# Arduino_Shield.net
KiCad netlist of a schematic drawn in EAGLE
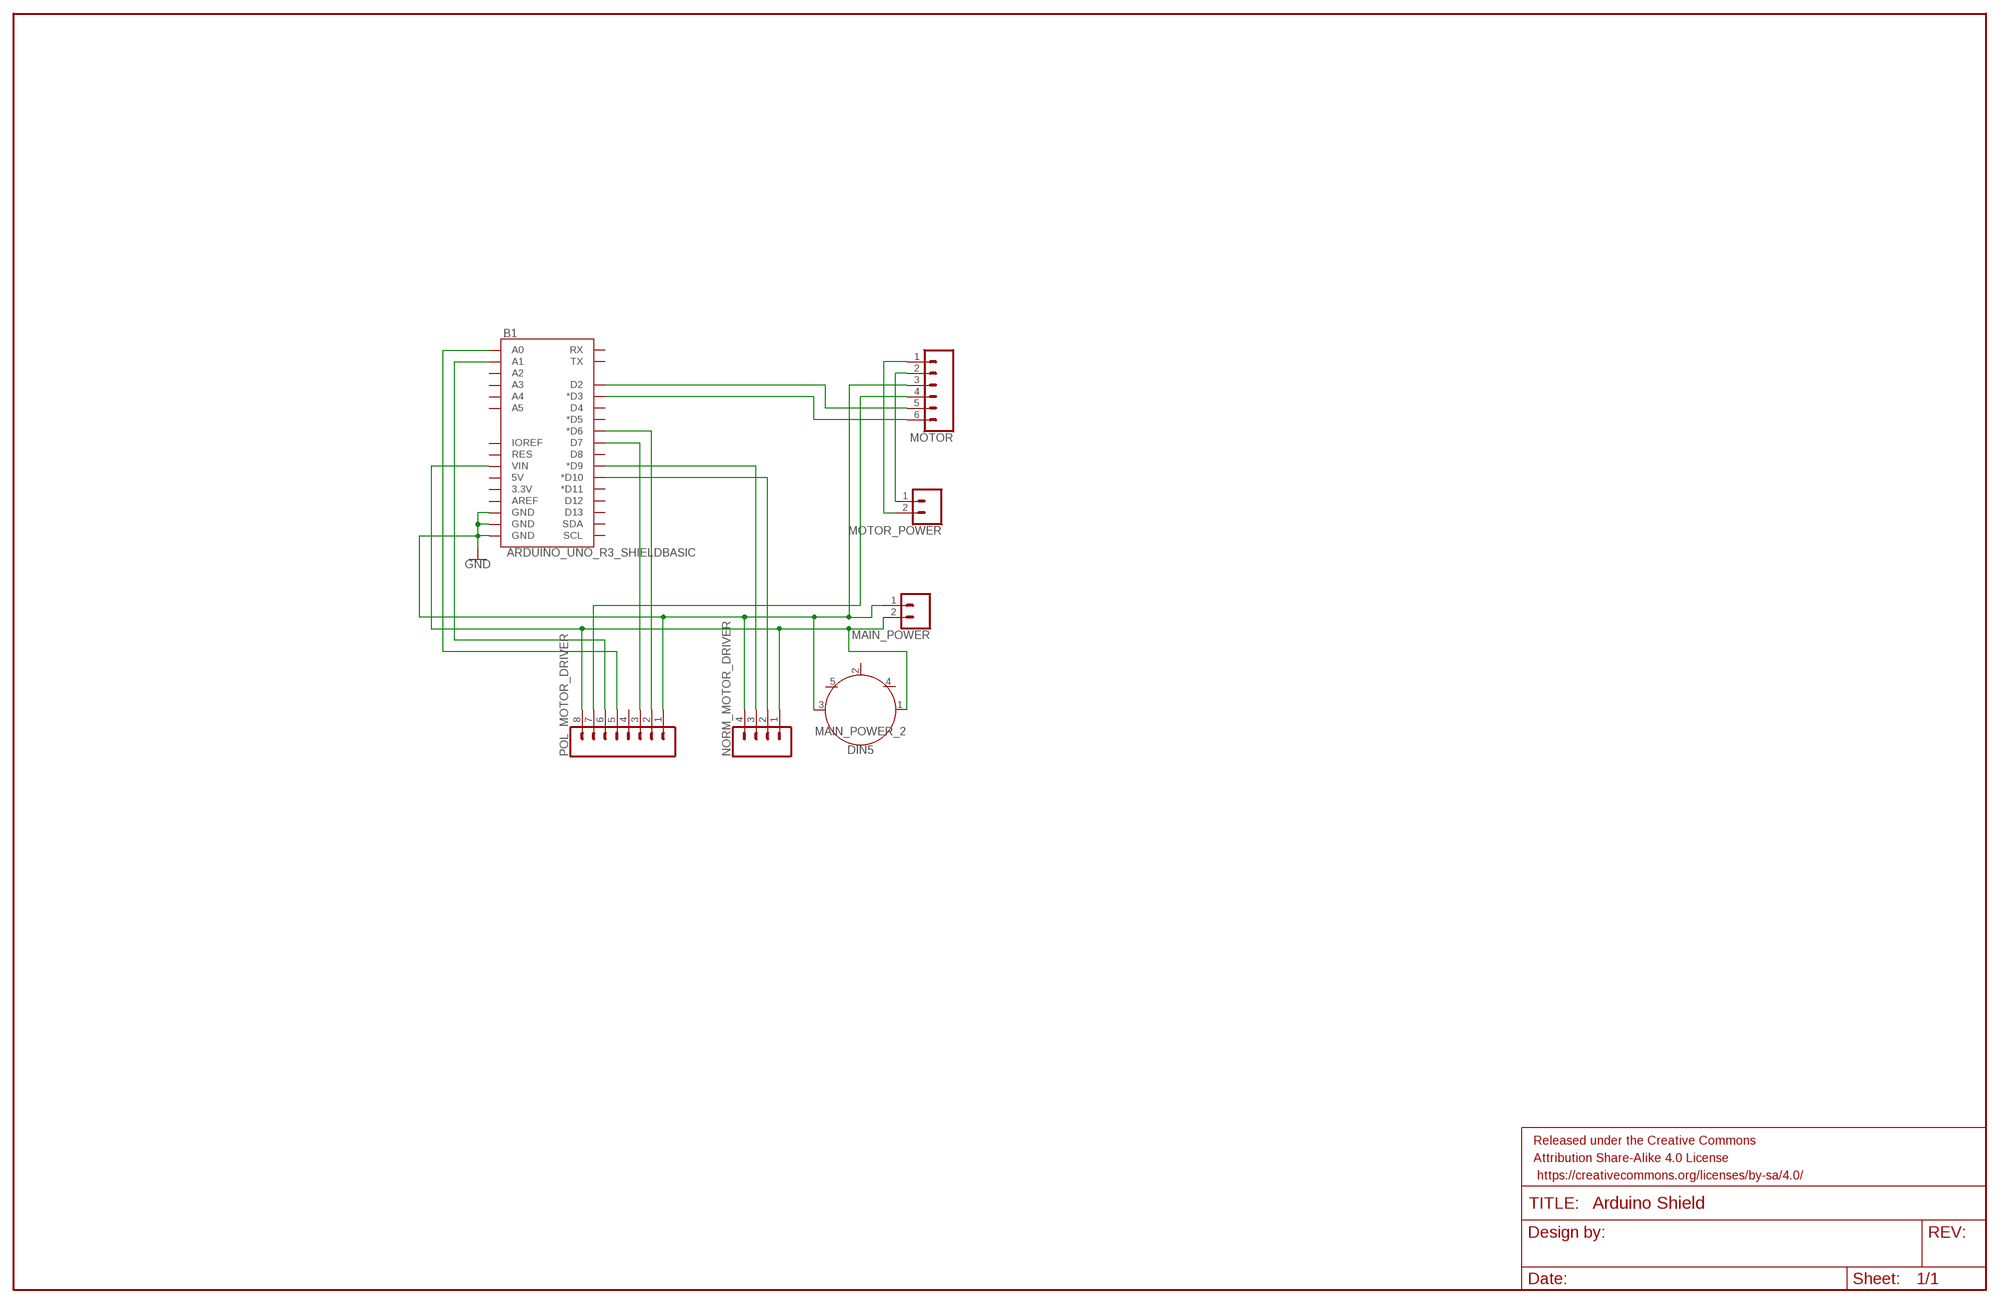
[diagram p0: schematic, sheet 1]

(export (version "E")
  (design (tool "Eeschema 10.0.6"))
  (components
    (comp (ref "B1")
      (value "ARDUINO_UNO_R3_SHIELDBASIC")
      (footprint "eagle-import:UNO_R3_SHIELD")
      (libsource (lib "eagle-import") (part "ARDUINO_UNO_R3_SHIELDBASIC"))
    )
    (comp (ref "FRAME1")
      (value "FRAME-LEDGER")
      (footprint "eagle-import:CREATIVE_COMMONS")
      (libsource (lib "eagle-import") (part "FRAME-LEDGER"))
    )
    (comp (ref "MAIN_POWER")
      (value "CONN_02-JST-2-PTH-NO_SILK")
      (footprint "eagle-import:JST-2-PTH-NS")
      (libsource (lib "eagle-import") (part "CONN_02-JST-2-PTH-NO_SILK"))
    )
    (comp (ref "MAIN_POWER_2")
      (value "DIN5")
      (footprint "eagle-import:DIN5-RA-PTH")
      (libsource (lib "eagle-import") (part "DIN5"))
    )
    (comp (ref "MOTOR")
      (value "CONN_06SILK_FEMALE_PTH")
      (footprint "eagle-import:1X06")
      (libsource (lib "eagle-import") (part "CONN_06SILK_FEMALE_PTH"))
    )
    (comp (ref "MOTOR_POWER")
      (value "CONN_02-JST-2-PTH-NO_SILK")
      (footprint "eagle-import:JST-2-PTH-NS")
      (libsource (lib "eagle-import") (part "CONN_02-JST-2-PTH-NO_SILK"))
    )
    (comp (ref "NORM_MOTOR_DRIVER")
      (value "CONN_04JST-PTH")
      (footprint "eagle-import:JST-4-PTH")
      (libsource (lib "eagle-import") (part "CONN_04JST-PTH"))
    )
    (comp (ref "POL_MOTOR_DRIVER")
      (value "CONN_08\"")
      (footprint "eagle-import:1X08")
      (libsource (lib "eagle-import") (part "CONN_08{dblquote}"))
    )
  )
  (nets
    (net (code "1") (name "GND") (class "Default")
      (node (ref "B1") (pin "GND@0") (pinfunction "GND_GND@0") (pintype "bidirectional"))
      (node (ref "B1") (pin "GND@1") (pinfunction "GND_GND@1") (pintype "bidirectional"))
      (node (ref "B1") (pin "GND@2") (pinfunction "GND_GND@2") (pintype "bidirectional"))
      (node (ref "MAIN_POWER") (pin "1") (pinfunction "1_1") (pintype "passive"))
      (node (ref "MAIN_POWER_2") (pin "3") (pinfunction "3_3") (pintype "bidirectional"))
      (node (ref "MOTOR") (pin "3") (pinfunction "3_3") (pintype "passive"))
      (node (ref "NORM_MOTOR_DRIVER") (pin "4") (pinfunction "4_4") (pintype "passive"))
      (node (ref "POL_MOTOR_DRIVER") (pin "1") (pinfunction "1_1") (pintype "passive"))
    )
    (net (code "2") (name "Net-(B1-*D3)") (class "Default")
      (node (ref "B1") (pin "D3") (pinfunction "*D3_D3") (pintype "bidirectional"))
      (node (ref "MOTOR") (pin "6") (pinfunction "6_6") (pintype "passive"))
    )
    (net (code "3") (name "Net-(B1-*D6)") (class "Default")
      (node (ref "B1") (pin "D6") (pinfunction "*D6_D6") (pintype "bidirectional"))
      (node (ref "POL_MOTOR_DRIVER") (pin "2") (pinfunction "2_2") (pintype "passive"))
    )
    (net (code "4") (name "Net-(B1-*D9)") (class "Default")
      (node (ref "B1") (pin "D9") (pinfunction "*D9_D9") (pintype "bidirectional"))
      (node (ref "NORM_MOTOR_DRIVER") (pin "3") (pinfunction "3_3") (pintype "passive"))
    )
    (net (code "5") (name "Net-(B1-*D10)") (class "Default")
      (node (ref "B1") (pin "D10") (pinfunction "*D10_D10") (pintype "bidirectional"))
      (node (ref "NORM_MOTOR_DRIVER") (pin "2") (pinfunction "2_2") (pintype "passive"))
    )
    (net (code "6") (name "Net-(B1-PadA0)") (class "Default")
      (node (ref "B1") (pin "A0") (pinfunction "A0_A0") (pintype "bidirectional"))
      (node (ref "POL_MOTOR_DRIVER") (pin "5") (pinfunction "5_5") (pintype "passive"))
    )
    (net (code "7") (name "Net-(B1-PadA1)") (class "Default")
      (node (ref "B1") (pin "A1") (pinfunction "A1_A1") (pintype "bidirectional"))
      (node (ref "POL_MOTOR_DRIVER") (pin "6") (pinfunction "6_6") (pintype "passive"))
    )
    (net (code "8") (name "Net-(B1-PadD2)") (class "Default")
      (node (ref "B1") (pin "D2") (pinfunction "D2_D2") (pintype "bidirectional"))
      (node (ref "MOTOR") (pin "5") (pinfunction "5_5") (pintype "passive"))
    )
    (net (code "9") (name "Net-(B1-PadD7)") (class "Default")
      (node (ref "B1") (pin "D7") (pinfunction "D7_D7") (pintype "bidirectional"))
      (node (ref "POL_MOTOR_DRIVER") (pin "3") (pinfunction "3_3") (pintype "passive"))
    )
    (net (code "10") (name "Net-(B1-PadVIN)") (class "Default")
      (node (ref "B1") (pin "VIN") (pinfunction "VIN_VIN") (pintype "bidirectional"))
      (node (ref "MAIN_POWER") (pin "2") (pinfunction "2_2") (pintype "passive"))
      (node (ref "MAIN_POWER_2") (pin "1") (pinfunction "1_1") (pintype "bidirectional"))
      (node (ref "NORM_MOTOR_DRIVER") (pin "1") (pinfunction "1_1") (pintype "passive"))
      (node (ref "POL_MOTOR_DRIVER") (pin "8") (pinfunction "8_8") (pintype "passive"))
    )
    (net (code "11") (name "Net-(MOTOR-Pad1)") (class "Default")
      (node (ref "MOTOR") (pin "1") (pinfunction "1_1") (pintype "passive"))
      (node (ref "MOTOR_POWER") (pin "2") (pinfunction "2_2") (pintype "passive"))
    )
    (net (code "12") (name "Net-(MOTOR-Pad2)") (class "Default")
      (node (ref "MOTOR") (pin "2") (pinfunction "2_2") (pintype "passive"))
      (node (ref "MOTOR_POWER") (pin "1") (pinfunction "1_1") (pintype "passive"))
    )
    (net (code "13") (name "Net-(MOTOR-Pad4)") (class "Default")
      (node (ref "MOTOR") (pin "4") (pinfunction "4_4") (pintype "passive"))
      (node (ref "POL_MOTOR_DRIVER") (pin "7") (pinfunction "7_7") (pintype "passive"))
    )
    (net (code "14") (name "unconnected-(B1-*D5-PadD5)") (class "Default")
      (node (ref "B1") (pin "D5") (pinfunction "*D5_D5") (pintype "bidirectional"))
    )
    (net (code "15") (name "unconnected-(B1-*D11-PadD11)") (class "Default")
      (node (ref "B1") (pin "D11") (pinfunction "*D11_D11") (pintype "bidirectional"))
    )
    (net (code "16") (name "unconnected-(B1-Pad3.3V)") (class "Default")
      (node (ref "B1") (pin "3.3V") (pinfunction "3.3V_3.3V") (pintype "bidirectional"))
    )
    (net (code "17") (name "unconnected-(B1-Pad5V)") (class "Default")
      (node (ref "B1") (pin "5V") (pinfunction "5V_5V") (pintype "bidirectional"))
    )
    (net (code "18") (name "unconnected-(B1-PadA2)") (class "Default")
      (node (ref "B1") (pin "A2") (pinfunction "A2_A2") (pintype "bidirectional"))
    )
    (net (code "19") (name "unconnected-(B1-PadA3)") (class "Default")
      (node (ref "B1") (pin "A3") (pinfunction "A3_A3") (pintype "bidirectional"))
    )
    (net (code "20") (name "unconnected-(B1-PadA4)") (class "Default")
      (node (ref "B1") (pin "A4") (pinfunction "A4_A4") (pintype "bidirectional"))
    )
    (net (code "21") (name "unconnected-(B1-PadA5)") (class "Default")
      (node (ref "B1") (pin "A5") (pinfunction "A5_A5") (pintype "bidirectional"))
    )
    (net (code "22") (name "unconnected-(B1-PadAREF)") (class "Default")
      (node (ref "B1") (pin "AREF") (pinfunction "AREF_AREF") (pintype "bidirectional"))
    )
    (net (code "23") (name "unconnected-(B1-PadD4)") (class "Default")
      (node (ref "B1") (pin "D4") (pinfunction "D4_D4") (pintype "bidirectional"))
    )
    (net (code "24") (name "unconnected-(B1-PadD8)") (class "Default")
      (node (ref "B1") (pin "D8") (pinfunction "D8_D8") (pintype "bidirectional"))
    )
    (net (code "25") (name "unconnected-(B1-PadD12)") (class "Default")
      (node (ref "B1") (pin "D12") (pinfunction "D12_D12") (pintype "bidirectional"))
    )
    (net (code "26") (name "unconnected-(B1-PadD13)") (class "Default")
      (node (ref "B1") (pin "D13") (pinfunction "D13_D13") (pintype "bidirectional"))
    )
    (net (code "27") (name "unconnected-(B1-PadIOREF)") (class "Default")
      (node (ref "B1") (pin "IOREF") (pinfunction "IOREF_IOREF") (pintype "bidirectional"))
    )
    (net (code "28") (name "unconnected-(B1-PadRES)") (class "Default")
      (node (ref "B1") (pin "RES") (pinfunction "RES_RES") (pintype "bidirectional"))
    )
    (net (code "29") (name "unconnected-(B1-PadRX)") (class "Default")
      (node (ref "B1") (pin "RX") (pinfunction "RX_RX") (pintype "bidirectional"))
    )
    (net (code "30") (name "unconnected-(B1-PadSCL)") (class "Default")
      (node (ref "B1") (pin "SCL") (pinfunction "SCL_SCL") (pintype "bidirectional"))
    )
    (net (code "31") (name "unconnected-(B1-PadSDA)") (class "Default")
      (node (ref "B1") (pin "SDA") (pinfunction "SDA_SDA") (pintype "bidirectional"))
    )
    (net (code "32") (name "unconnected-(B1-PadTX)") (class "Default")
      (node (ref "B1") (pin "TX") (pinfunction "TX_TX") (pintype "bidirectional"))
    )
    (net (code "33") (name "unconnected-(MAIN_POWER_2-Pad2)") (class "Default")
      (node (ref "MAIN_POWER_2") (pin "2") (pinfunction "2_2") (pintype "bidirectional"))
    )
    (net (code "34") (name "unconnected-(MAIN_POWER_2-Pad4)") (class "Default")
      (node (ref "MAIN_POWER_2") (pin "4") (pinfunction "4_4") (pintype "bidirectional"))
    )
    (net (code "35") (name "unconnected-(MAIN_POWER_2-Pad5)") (class "Default")
      (node (ref "MAIN_POWER_2") (pin "5") (pinfunction "5_5") (pintype "bidirectional"))
    )
    (net (code "36") (name "unconnected-(POL_MOTOR_DRIVER-Pad4)") (class "Default")
      (node (ref "POL_MOTOR_DRIVER") (pin "4") (pinfunction "4_4") (pintype "passive"))
    )
  )
)
